# Buck_Regulator_Schematic.net
KiCad netlist of a schematic drawn in Altium Designer
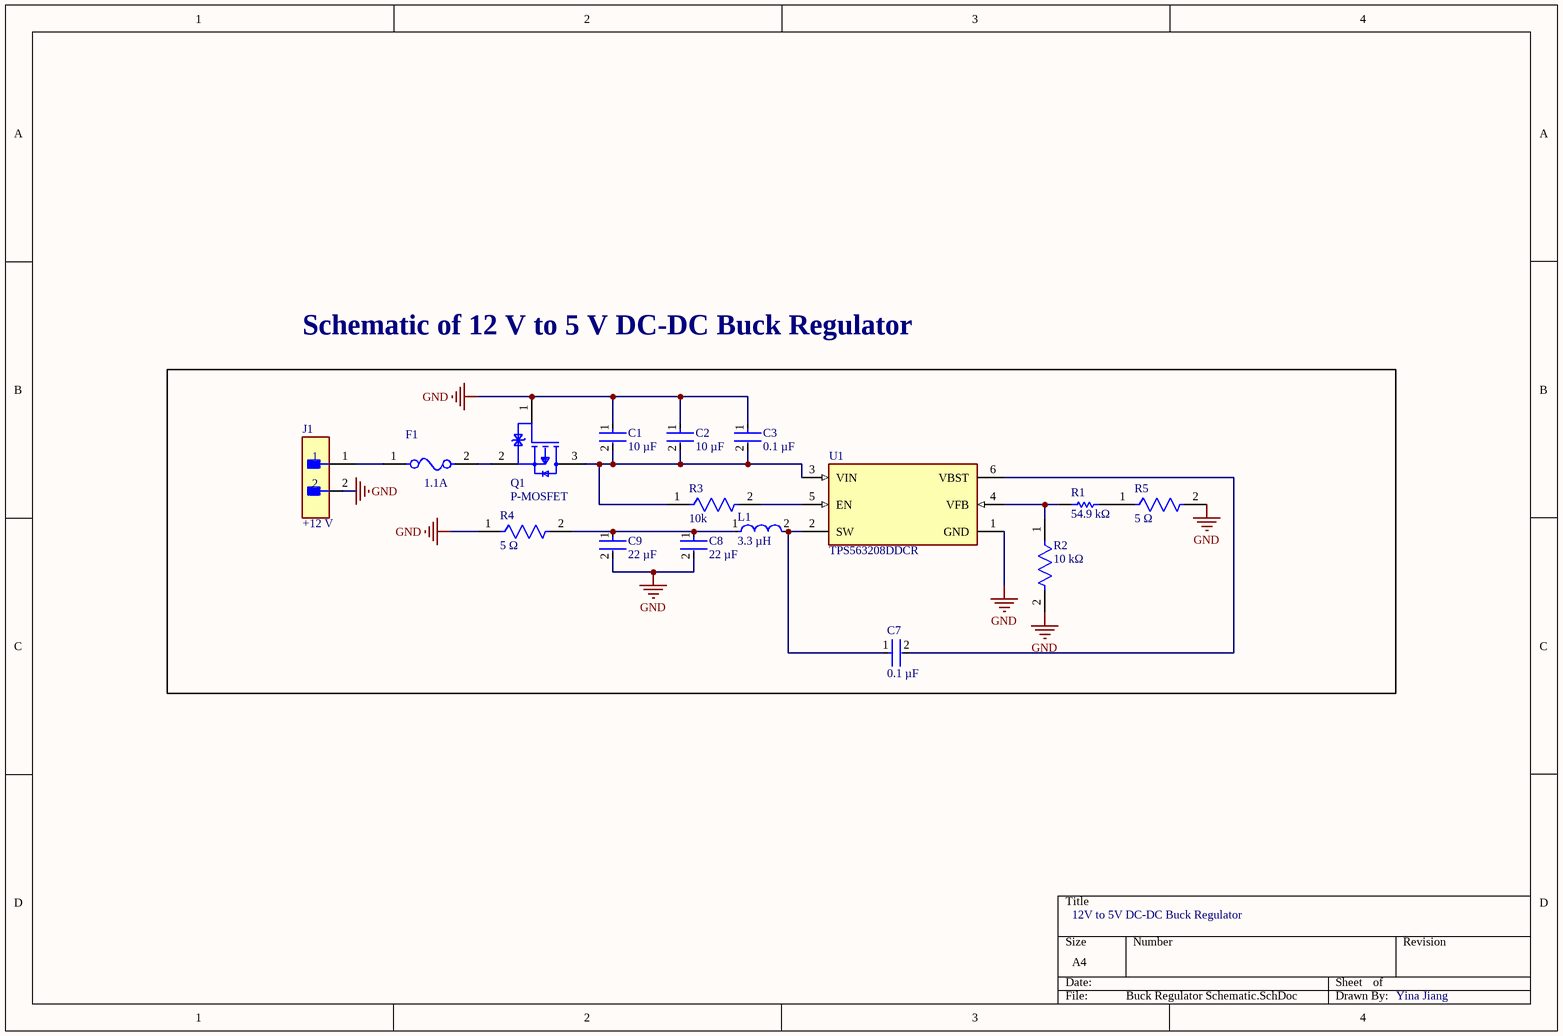
[diagram p0: Buck Regulator Schematic.SchDoc]

(export (version "E")
  (design (tool "Eeschema 10.0.6"))
  (components
    (comp (ref "C1")
      (value "10 µF")
      (footprint "FP-CC0805-EB-IPC_C")
      (description "CAP CER 10UF 10V X7R 0805")
      (fields (field (name "TOLERANCE") "10%"))
      (libsource (lib "Altium Content Vault") (part "b4654b650e69147ec39a6b967a45e02"))
    )
    (comp (ref "C2")
      (value "10 µF")
      (footprint "FP-CC0805-EB-IPC_C")
      (description "CAP CER 10UF 10V X7R 0805")
      (fields (field (name "TOLERANCE") "10%"))
      (libsource (lib "Altium Content Vault") (part "b4654b650e69147ec39a6b967a45e02"))
    )
    (comp (ref "C3")
      (value "0.1 µF")
      (footprint "FP-AC0805-0_85-MFG")
      (description "0.10µF 50V Ceramic Capacitor X7R 0805 (2012 Metric) 0.079\" L x 0.049\" W (2.00mm x 1.25mm)")
      (fields
        (field (name "TOLERANCE") "0.1")
        (field (name "OCTOPART") "https://octopart.com/ac0805krx7r9bb104-yageo-71334198")
      )
      (libsource (lib "Altium Content Vault") (part "11868f565c42a9108669ba33697ecf6"))
    )
    (comp (ref "C7")
      (value "0.1 µF")
      (footprint "FP-AC0805-0_85-MFG")
      (description "0.10µF 50V Ceramic Capacitor X7R 0805 (2012 Metric) 0.079\" L x 0.049\" W (2.00mm x 1.25mm)")
      (fields
        (field (name "TOLERANCE") "0.1")
        (field (name "OCTOPART") "https://octopart.com/ac0805krx7r9bb104-yageo-71334198")
      )
      (libsource (lib "Altium Content Vault") (part "11868f565c42a9108669ba33697ecf6"))
    )
    (comp (ref "C8")
      (value "22 µF")
      (footprint "FP-GCM31C-0_2-e0_3_0_8-MFG")
      (description "GCM31CD70J226KE02K Multilayer Ceramic Capacitors MLCC - SMD/SMT 1206 6.3VDC 22 F 10 X7T AEC-Q200")
      (fields (field (name "TOLERANCE") "10%"))
      (libsource (lib "Altium Content Vault") (part "b4654b650e69147ec39a6b967a45e02"))
    )
    (comp (ref "C9")
      (value "22 µF")
      (footprint "FP-GCM31C-0_2-e0_3_0_8-MFG")
      (description "GCM31CD70J226KE02K Multilayer Ceramic Capacitors MLCC - SMD/SMT 1206 6.3VDC 22 F 10 X7T AEC-Q200")
      (fields (field (name "TOLERANCE") "10%"))
      (libsource (lib "Altium Content Vault") (part "b4654b650e69147ec39a6b967a45e02"))
    )
    (comp (ref "F1")
      (value "1.1A")
      (footprint "FP-MF-MSMF110-16-MFG")
      (description "PTC RESET FUSE 16V 1.1A 1812")
      (fields
        (field (name "OCTOPART") "https://octopart.com/mf-msmf110%2F16-2-bourns-40767")
        (field (name "MANUFACTURER PART NUMBER") "MF-MSMF110/16-2")
      )
      (libsource (lib "Altium Content Vault") (part "5bcf9b9f640e542cf0359d10258e979"))
    )
    (comp (ref "J1")
      (value "+12 V")
      (footprint "FP-1776508-MFG")
      (description "TERM BLOCK HDR 2POS 90DEG 5.08MM")
      (fields (field (name "VOLTAGE") "300V"))
      (libsource (lib "Altium Content Vault") (part "3bc925449376181038e59eaffc5286c"))
    )
    (comp (ref "L1")
      (value "3.3 µH")
      (footprint "FP-IHLP-2525CZ-FP_2_413x3-MFG")
      (description "Tin / Lead Inductors, High Saturation Series 3.3uH 6A 30mΩ 20%")
      (libsource (lib "Altium Content Vault") (part "725321dda6339637d4d059423bc1c3c"))
    )
    (comp (ref "Q1")
      (value "P-MOSFET")
      (footprint "FP-SOT23-MFG")
      (description "MOSFET P-CH 20V 600MA SOT23-3")
      (fields
        (field (name "MANUFACTURER PART NUMBER") "DMP2004K-7")
        (field (name "OCTOPART") "https://octopart.com/dmp2004k-7-diodes+inc.-7151877")
      )
      (libsource (lib "Altium Content Vault") (part "0909edbb8d389a8e80b8543cd1a9d7a"))
    )
    (comp (ref "R1")
      (value "54.9 kΩ")
      (footprint "RESC2512(6432)_M")
      (description "54K9 1W 1% 2512 (6432 Metric)  SMD")
      (fields (field (name "TOLERANCE") "1 %") (field (name "POWER") "1 W"))
      (libsource (lib "Altium Content Vault") (part "RES"))
    )
    (comp (ref "R2")
      (value "10 kΩ")
      (footprint "FP-AC0603-IPC_A")
      (description "RES 10kΩ 5.00% 0.2W 0603")
      (libsource (lib "Altium Content Vault") (part "1029c3af85768c4190bb7ad29bc67b5"))
    )
    (comp (ref "R3")
      (value "10k")
      (footprint "FP-AC0603-IPC_A")
      (description "RES 10kΩ 5.00% 0.2W 0603")
      (libsource (lib "Altium Content Vault") (part "1029c3af85768c4190bb7ad29bc67b5"))
    )
    (comp (ref "R4")
      (value "5 Ω")
      (footprint "FP-RLT1220-F-MFG")
      (description "RES SMD 5 OHM 1% 1/3W 0805")
      (libsource (lib "Altium Content Vault") (part "1029c3af85768c4190bb7ad29bc67b5"))
    )
    (comp (ref "R5")
      (value "5 Ω")
      (footprint "FP-RLT1220-F-MFG")
      (description "RES SMD 5 OHM 1% 1/3W 0805")
      (libsource (lib "Altium Content Vault") (part "1029c3af85768c4190bb7ad29bc67b5"))
    )
    (comp (ref "U1")
      (value "TPS563208DDCR")
      (footprint "FP-DDC0006A-MFG")
      (description "IC REG BUCK ADJ 3A TSOT23-6")
      (libsource (lib "Altium Content Vault") (part "aba72cbc9cf0ad42a1bc8855c06655c"))
    )
  )
  (nets
    (net (code "1") (name "GND") (class "Default")
      (node (ref "C1") (pin "1") (pinfunction "1_1") (pintype "passive"))
      (node (ref "C2") (pin "1") (pinfunction "1_1") (pintype "passive"))
      (node (ref "C3") (pin "1") (pinfunction "1_1") (pintype "passive"))
      (node (ref "C8") (pin "2") (pinfunction "2_2") (pintype "passive"))
      (node (ref "C9") (pin "2") (pinfunction "2_2") (pintype "passive"))
      (node (ref "J1") (pin "2") (pinfunction "2_2") (pintype "passive"))
      (node (ref "Q1") (pin "1") (pinfunction "G_1") (pintype "passive"))
      (node (ref "R2") (pin "2") (pinfunction "2_2") (pintype "passive"))
      (node (ref "R4") (pin "1") (pinfunction "1_1") (pintype "passive"))
      (node (ref "R5") (pin "2") (pinfunction "2_2") (pintype "passive"))
      (node (ref "U1") (pin "1") (pinfunction "GND_1") (pintype "power_in"))
    )
    (net (code "2") (name "Net-(C8-Pad1)") (class "Default")
      (node (ref "C8") (pin "1") (pinfunction "1_1") (pintype "passive"))
      (node (ref "C9") (pin "1") (pinfunction "1_1") (pintype "passive"))
      (node (ref "L1") (pin "1") (pinfunction "1_1") (pintype "passive"))
      (node (ref "R4") (pin "2") (pinfunction "2_2") (pintype "passive"))
    )
    (net (code "3") (name "Net-(F1-Pad1)") (class "Default")
      (node (ref "F1") (pin "1") (pinfunction "1_1") (pintype "passive"))
      (node (ref "J1") (pin "1") (pinfunction "1_1") (pintype "passive"))
    )
    (net (code "4") (name "Net-(Q1-D)") (class "Default")
      (node (ref "C1") (pin "2") (pinfunction "2_2") (pintype "passive"))
      (node (ref "C2") (pin "2") (pinfunction "2_2") (pintype "passive"))
      (node (ref "C3") (pin "2") (pinfunction "2_2") (pintype "passive"))
      (node (ref "Q1") (pin "3") (pinfunction "D_3") (pintype "passive"))
      (node (ref "R3") (pin "1") (pinfunction "1_1") (pintype "passive"))
      (node (ref "U1") (pin "3") (pinfunction "VIN_3") (pintype "input"))
    )
    (net (code "5") (name "Net-(Q1-S)") (class "Default")
      (node (ref "F1") (pin "2") (pinfunction "2_2") (pintype "passive"))
      (node (ref "Q1") (pin "2") (pinfunction "S_2") (pintype "passive"))
    )
    (net (code "6") (name "Net-(R1-Pad2)") (class "Default")
      (node (ref "R1") (pin "2") (pinfunction "2_2") (pintype "passive"))
      (node (ref "R5") (pin "1") (pinfunction "1_1") (pintype "passive"))
    )
    (net (code "7") (name "Net-(U1-EN)") (class "Default")
      (node (ref "R3") (pin "2") (pinfunction "2_2") (pintype "passive"))
      (node (ref "U1") (pin "5") (pinfunction "EN_5") (pintype "input"))
    )
    (net (code "8") (name "Net-(U1-SW)") (class "Default")
      (node (ref "C7") (pin "1") (pinfunction "1_1") (pintype "passive"))
      (node (ref "L1") (pin "2") (pinfunction "2_2") (pintype "passive"))
      (node (ref "U1") (pin "2") (pinfunction "SW_2") (pintype "power_in"))
    )
    (net (code "9") (name "Net-(U1-VBST)") (class "Default")
      (node (ref "C7") (pin "2") (pinfunction "2_2") (pintype "passive"))
      (node (ref "U1") (pin "6") (pinfunction "VBST_6") (pintype "power_in"))
    )
    (net (code "10") (name "Net-(U1-VFB)") (class "Default")
      (node (ref "R1") (pin "1") (pinfunction "1_1") (pintype "passive"))
      (node (ref "R2") (pin "1") (pinfunction "1_1") (pintype "passive"))
      (node (ref "U1") (pin "4") (pinfunction "VFB_4") (pintype "input"))
    )
  )
)
